# mainboard.net
KiCad netlist of a schematic drawn in EAGLE
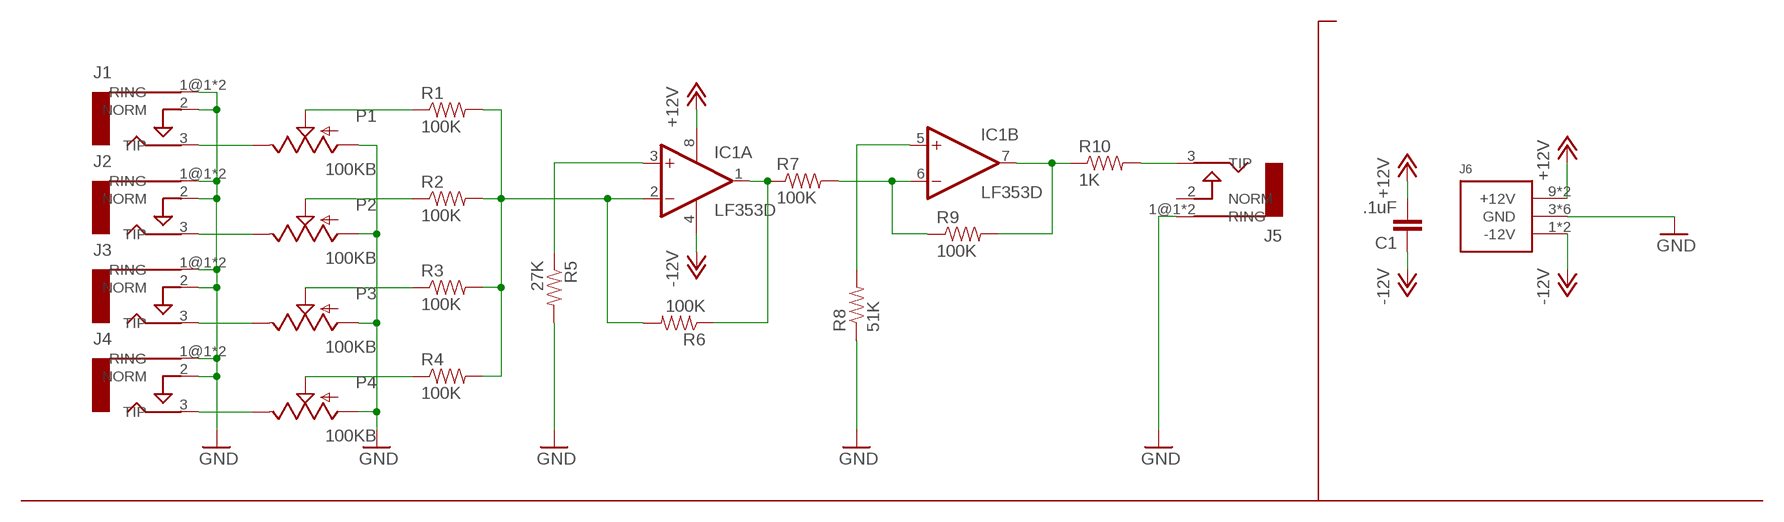
[diagram p0: schematic, sheet 1]

(export (version "E")
  (design (tool "Eeschema 10.0.6"))
  (components
    (comp (ref "C1")
      (value ".1uF")
      (footprint "eagle-import:0603-CAP")
      (libsource (lib "eagle-import") (part "CAP0603-CAP"))
    )
    (comp (ref "IC1")
      (value "LF353D")
      (footprint "eagle-import:SO08")
      (libsource (lib "eagle-import") (part "LF353D"))
    )
    (comp (ref "J1")
      (value "AUDIO-JACKERTHENVAR")
      (footprint "eagle-import:ERTHENVAR-JACK")
      (libsource (lib "eagle-import") (part "AUDIO-JACKERTHENVAR"))
    )
    (comp (ref "J2")
      (value "AUDIO-JACKERTHENVAR")
      (footprint "eagle-import:ERTHENVAR-JACK")
      (libsource (lib "eagle-import") (part "AUDIO-JACKERTHENVAR"))
    )
    (comp (ref "J3")
      (value "AUDIO-JACKERTHENVAR")
      (footprint "eagle-import:ERTHENVAR-JACK")
      (libsource (lib "eagle-import") (part "AUDIO-JACKERTHENVAR"))
    )
    (comp (ref "J4")
      (value "AUDIO-JACKERTHENVAR")
      (footprint "eagle-import:ERTHENVAR-JACK")
      (libsource (lib "eagle-import") (part "AUDIO-JACKERTHENVAR"))
    )
    (comp (ref "J5")
      (value "AUDIO-JACKERTHENVAR")
      (footprint "eagle-import:ERTHENVAR-JACK")
      (libsource (lib "eagle-import") (part "AUDIO-JACKERTHENVAR"))
    )
    (comp (ref "J6")
      (value "POWER_SIMPLE16")
      (footprint "eagle-import:POWER_16")
      (libsource (lib "eagle-import") (part "POWER_SIMPLE16"))
    )
    (comp (ref "P1")
      (value "100KB")
      (footprint "eagle-import:PDB12")
      (libsource (lib "eagle-import") (part "POTPDB12"))
    )
    (comp (ref "P2")
      (value "100KB")
      (footprint "eagle-import:PDB12")
      (libsource (lib "eagle-import") (part "POTPDB12"))
    )
    (comp (ref "P3")
      (value "100KB")
      (footprint "eagle-import:PDB12")
      (libsource (lib "eagle-import") (part "POTPDB12"))
    )
    (comp (ref "P4")
      (value "100KB")
      (footprint "eagle-import:PDB12")
      (libsource (lib "eagle-import") (part "POTPDB12"))
    )
    (comp (ref "R1")
      (value "100K")
      (footprint "eagle-import:0603-RES")
      (libsource (lib "eagle-import") (part "1.2MOHMS-1/10W-1%(0603)"))
    )
    (comp (ref "R2")
      (value "100K")
      (footprint "eagle-import:0603-RES")
      (libsource (lib "eagle-import") (part "1.2MOHMS-1/10W-1%(0603)"))
    )
    (comp (ref "R3")
      (value "100K")
      (footprint "eagle-import:0603-RES")
      (libsource (lib "eagle-import") (part "1.2MOHMS-1/10W-1%(0603)"))
    )
    (comp (ref "R4")
      (value "100K")
      (footprint "eagle-import:0603-RES")
      (libsource (lib "eagle-import") (part "1.2MOHMS-1/10W-1%(0603)"))
    )
    (comp (ref "R5")
      (value "27K")
      (footprint "eagle-import:0603-RES")
      (libsource (lib "eagle-import") (part "1.2MOHMS-1/10W-1%(0603)"))
    )
    (comp (ref "R6")
      (value "100K")
      (footprint "eagle-import:0603-RES")
      (libsource (lib "eagle-import") (part "1.2MOHMS-1/10W-1%(0603)"))
    )
    (comp (ref "R7")
      (value "100K")
      (footprint "eagle-import:0603-RES")
      (libsource (lib "eagle-import") (part "1.2MOHMS-1/10W-1%(0603)"))
    )
    (comp (ref "R8")
      (value "51K")
      (footprint "eagle-import:0603-RES")
      (libsource (lib "eagle-import") (part "1.2MOHMS-1/10W-1%(0603)"))
    )
    (comp (ref "R9")
      (value "100K")
      (footprint "eagle-import:0603-RES")
      (libsource (lib "eagle-import") (part "1.2MOHMS-1/10W-1%(0603)"))
    )
    (comp (ref "R10")
      (value "1K")
      (footprint "eagle-import:0603-RES")
      (libsource (lib "eagle-import") (part "1.2MOHMS-1/10W-1%(0603)"))
    )
  )
  (nets
    (net (code "1") (name "+12V") (class "Default")
      (node (ref "C1") (pin "2") (pinfunction "2_2") (pintype "passive"))
      (node (ref "IC1") (pin "8") (pinfunction "V+_8") (pintype "power_in"))
      (node (ref "J6") (pin "10") (pinfunction "+12V_10") (pintype "bidirectional"))
      (node (ref "J6") (pin "9") (pinfunction "+12V_9") (pintype "bidirectional"))
    )
    (net (code "2") (name "-12V") (class "Default")
      (node (ref "C1") (pin "1") (pinfunction "1_1") (pintype "passive"))
      (node (ref "IC1") (pin "4") (pinfunction "V-_4") (pintype "power_in"))
      (node (ref "J6") (pin "1") (pinfunction "-12V_1") (pintype "bidirectional"))
      (node (ref "J6") (pin "2") (pinfunction "-12V_2") (pintype "bidirectional"))
    )
    (net (code "3") (name "GND") (class "Default")
      (node (ref "J1") (pin "1@1") (pinfunction "RING_1@1") (pintype "bidirectional"))
      (node (ref "J1") (pin "1@2") (pinfunction "RING_1@2") (pintype "bidirectional"))
      (node (ref "J1") (pin "2") (pinfunction "NORM_2") (pintype "bidirectional"))
      (node (ref "J2") (pin "1@1") (pinfunction "RING_1@1") (pintype "bidirectional"))
      (node (ref "J2") (pin "1@2") (pinfunction "RING_1@2") (pintype "bidirectional"))
      (node (ref "J2") (pin "2") (pinfunction "NORM_2") (pintype "bidirectional"))
      (node (ref "J3") (pin "1@1") (pinfunction "RING_1@1") (pintype "bidirectional"))
      (node (ref "J3") (pin "1@2") (pinfunction "RING_1@2") (pintype "bidirectional"))
      (node (ref "J3") (pin "2") (pinfunction "NORM_2") (pintype "bidirectional"))
      (node (ref "J4") (pin "1@1") (pinfunction "RING_1@1") (pintype "bidirectional"))
      (node (ref "J4") (pin "1@2") (pinfunction "RING_1@2") (pintype "bidirectional"))
      (node (ref "J4") (pin "2") (pinfunction "NORM_2") (pintype "bidirectional"))
      (node (ref "J5") (pin "1@1") (pinfunction "RING_1@1") (pintype "bidirectional"))
      (node (ref "J5") (pin "1@2") (pinfunction "RING_1@2") (pintype "bidirectional"))
      (node (ref "J6") (pin "3") (pinfunction "GND_3") (pintype "bidirectional"))
      (node (ref "J6") (pin "4") (pinfunction "GND_4") (pintype "bidirectional"))
      (node (ref "J6") (pin "5") (pinfunction "GND_5") (pintype "bidirectional"))
      (node (ref "J6") (pin "6") (pinfunction "GND_6") (pintype "bidirectional"))
      (node (ref "J6") (pin "7") (pinfunction "GND_7") (pintype "bidirectional"))
      (node (ref "J6") (pin "8") (pinfunction "GND_8") (pintype "bidirectional"))
      (node (ref "P1") (pin "1") (pinfunction "A_1") (pintype "passive"))
      (node (ref "P2") (pin "1") (pinfunction "A_1") (pintype "passive"))
      (node (ref "P3") (pin "1") (pinfunction "A_1") (pintype "passive"))
      (node (ref "P4") (pin "1") (pinfunction "A_1") (pintype "passive"))
      (node (ref "R5") (pin "2") (pinfunction "2_2") (pintype "passive"))
      (node (ref "R8") (pin "1") (pinfunction "1_1") (pintype "passive"))
    )
    (net (code "4") (name "Net-(IC1A-+IN)") (class "Default")
      (node (ref "IC1") (pin "3") (pinfunction "+IN_3") (pintype "input"))
      (node (ref "R5") (pin "1") (pinfunction "1_1") (pintype "passive"))
    )
    (net (code "5") (name "Net-(IC1A--IN)") (class "Default")
      (node (ref "IC1") (pin "2") (pinfunction "-IN_2") (pintype "input"))
      (node (ref "R1") (pin "2") (pinfunction "2_2") (pintype "passive"))
      (node (ref "R2") (pin "2") (pinfunction "2_2") (pintype "passive"))
      (node (ref "R3") (pin "2") (pinfunction "2_2") (pintype "passive"))
      (node (ref "R4") (pin "2") (pinfunction "2_2") (pintype "passive"))
      (node (ref "R6") (pin "2") (pinfunction "2_2") (pintype "passive"))
    )
    (net (code "6") (name "Net-(IC1A-OUT)") (class "Default")
      (node (ref "IC1") (pin "1") (pinfunction "OUT_1") (pintype "output"))
      (node (ref "R6") (pin "1") (pinfunction "1_1") (pintype "passive"))
      (node (ref "R7") (pin "1") (pinfunction "1_1") (pintype "passive"))
    )
    (net (code "7") (name "Net-(IC1B-+IN)") (class "Default")
      (node (ref "IC1") (pin "5") (pinfunction "+IN_5") (pintype "input"))
      (node (ref "R8") (pin "2") (pinfunction "2_2") (pintype "passive"))
    )
    (net (code "8") (name "Net-(IC1B--IN)") (class "Default")
      (node (ref "IC1") (pin "6") (pinfunction "-IN_6") (pintype "input"))
      (node (ref "R7") (pin "2") (pinfunction "2_2") (pintype "passive"))
      (node (ref "R9") (pin "1") (pinfunction "1_1") (pintype "passive"))
    )
    (net (code "9") (name "Net-(IC1B-OUT)") (class "Default")
      (node (ref "IC1") (pin "7") (pinfunction "OUT_7") (pintype "output"))
      (node (ref "R10") (pin "1") (pinfunction "1_1") (pintype "passive"))
      (node (ref "R9") (pin "2") (pinfunction "2_2") (pintype "passive"))
    )
    (net (code "10") (name "Net-(J1-TIP)") (class "Default")
      (node (ref "J1") (pin "3") (pinfunction "TIP_3") (pintype "bidirectional"))
      (node (ref "P1") (pin "3") (pinfunction "E_3") (pintype "passive"))
    )
    (net (code "11") (name "Net-(J2-TIP)") (class "Default")
      (node (ref "J2") (pin "3") (pinfunction "TIP_3") (pintype "bidirectional"))
      (node (ref "P2") (pin "3") (pinfunction "E_3") (pintype "passive"))
    )
    (net (code "12") (name "Net-(J3-TIP)") (class "Default")
      (node (ref "J3") (pin "3") (pinfunction "TIP_3") (pintype "bidirectional"))
      (node (ref "P3") (pin "3") (pinfunction "E_3") (pintype "passive"))
    )
    (net (code "13") (name "Net-(J4-TIP)") (class "Default")
      (node (ref "J4") (pin "3") (pinfunction "TIP_3") (pintype "bidirectional"))
      (node (ref "P4") (pin "3") (pinfunction "E_3") (pintype "passive"))
    )
    (net (code "14") (name "Net-(J5-TIP)") (class "Default")
      (node (ref "J5") (pin "3") (pinfunction "TIP_3") (pintype "bidirectional"))
      (node (ref "R10") (pin "2") (pinfunction "2_2") (pintype "passive"))
    )
    (net (code "15") (name "Net-(P1-S)") (class "Default")
      (node (ref "P1") (pin "2") (pinfunction "S_2") (pintype "passive"))
      (node (ref "R1") (pin "1") (pinfunction "1_1") (pintype "passive"))
    )
    (net (code "16") (name "Net-(P2-S)") (class "Default")
      (node (ref "P2") (pin "2") (pinfunction "S_2") (pintype "passive"))
      (node (ref "R2") (pin "1") (pinfunction "1_1") (pintype "passive"))
    )
    (net (code "17") (name "Net-(P3-S)") (class "Default")
      (node (ref "P3") (pin "2") (pinfunction "S_2") (pintype "passive"))
      (node (ref "R3") (pin "1") (pinfunction "1_1") (pintype "passive"))
    )
    (net (code "18") (name "Net-(P4-S)") (class "Default")
      (node (ref "P4") (pin "2") (pinfunction "S_2") (pintype "passive"))
      (node (ref "R4") (pin "1") (pinfunction "1_1") (pintype "passive"))
    )
    (net (code "19") (name "unconnected-(J5-NORM-Pad2)") (class "Default")
      (node (ref "J5") (pin "2") (pinfunction "NORM_2") (pintype "bidirectional"))
    )
  )
)
